# E-bookReader.net
KiCad netlist of a schematic drawn in EAGLE
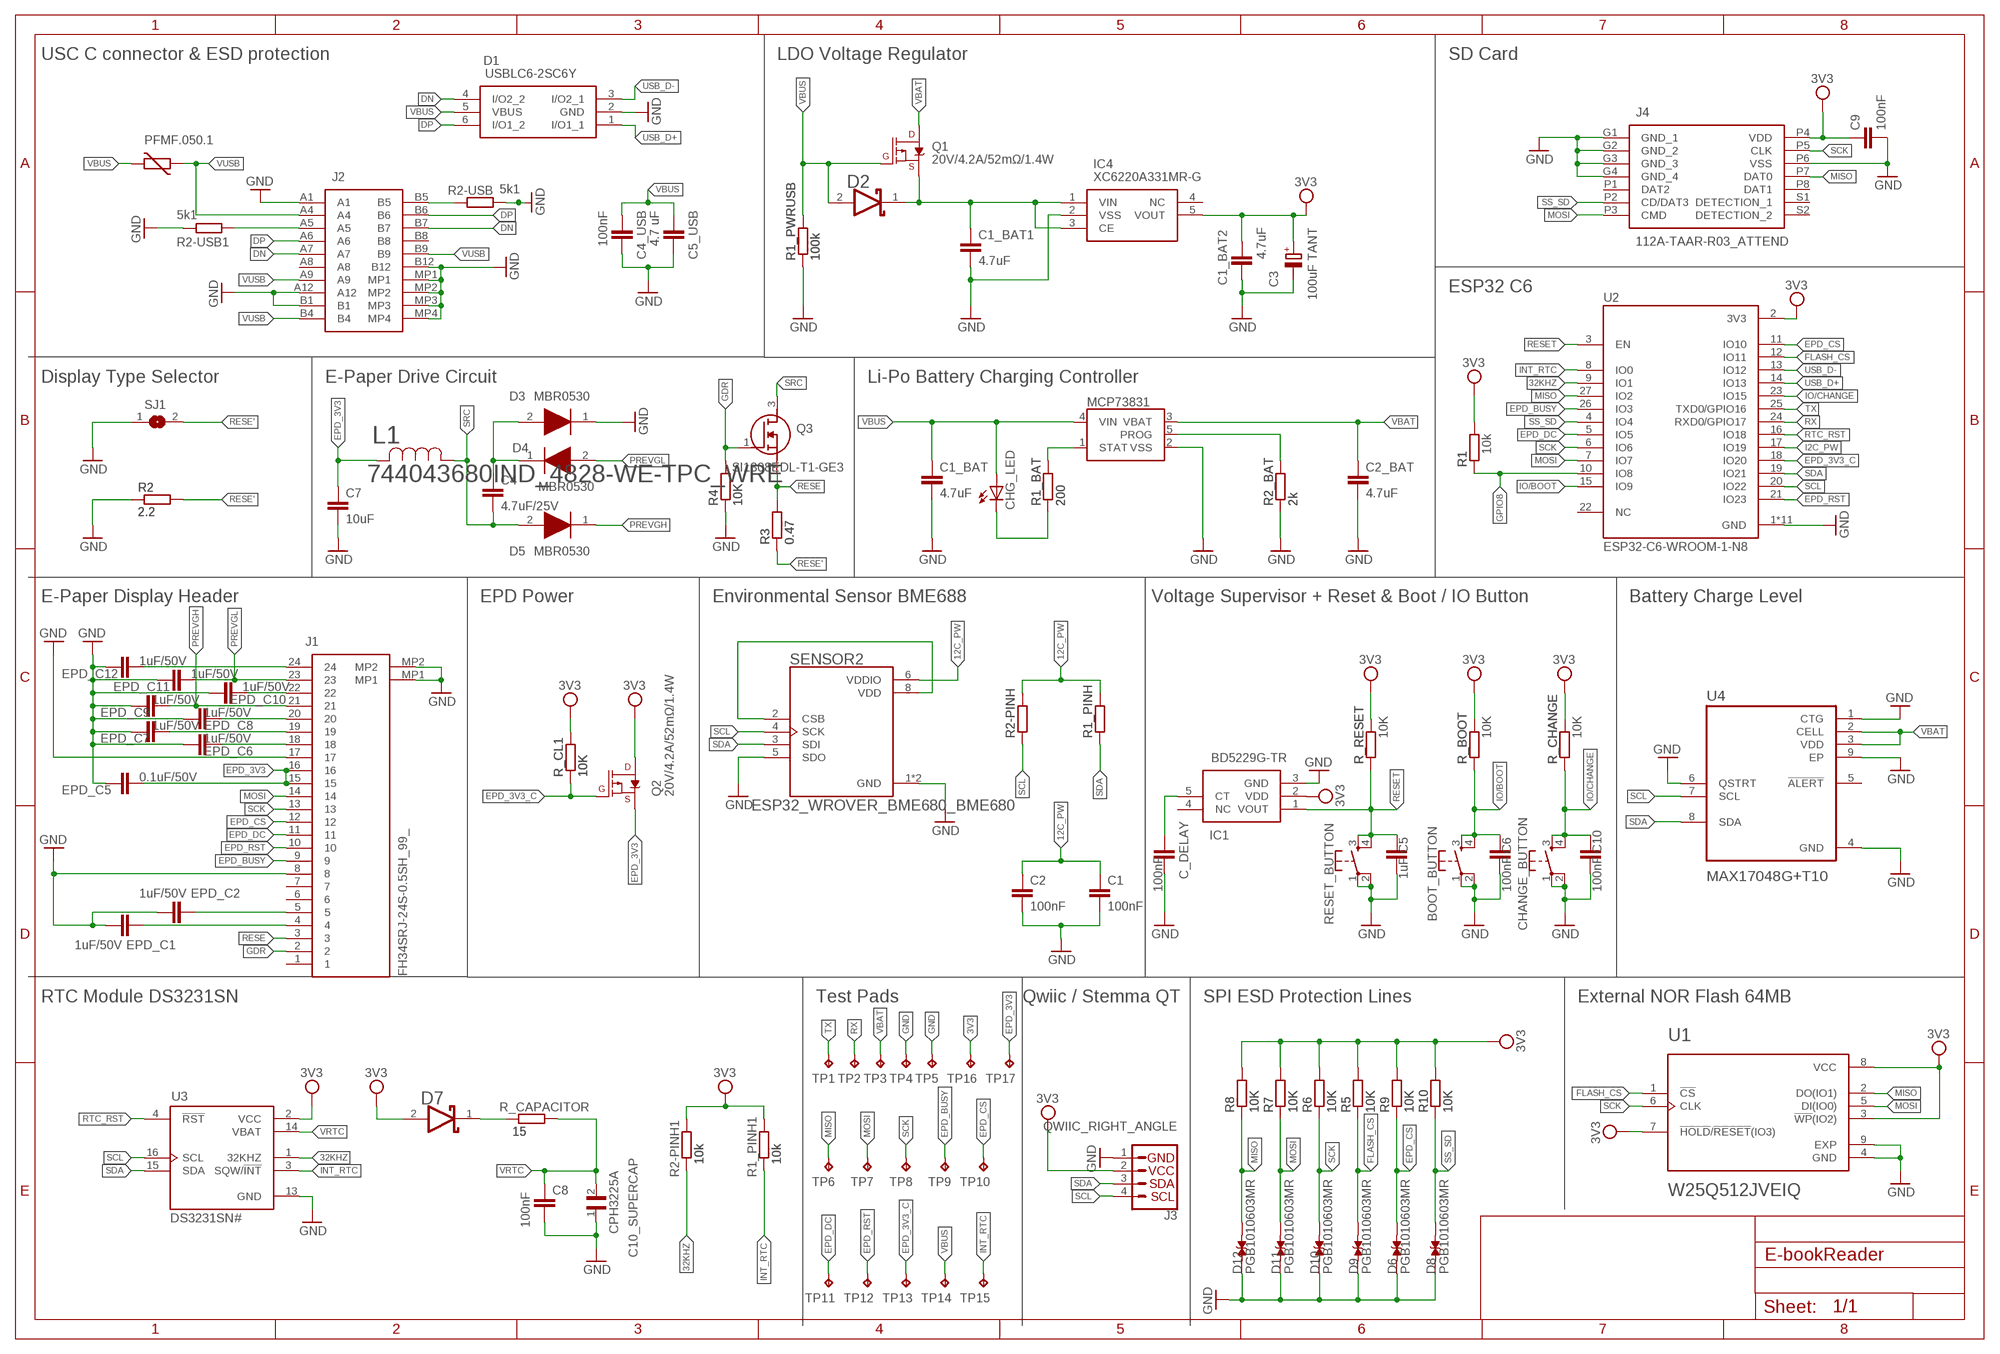
[diagram p0: schematic, sheet 1]

(export (version "E")
  (design (tool "Eeschema 10.0.6"))
  (components
    (comp (ref "BOOT_BUTTON")
      (value "BUTTON_CUSYOMV1")
      (footprint "eagle-import:MYBUTTON")
      (libsource (lib "eagle-import") (part "BUTTON_CUSYOMV1"))
    )
    (comp (ref "C1")
      (value "100nF")
      (footprint "eagle-import:EAGLE-LTSPICE_C0402")
      (libsource (lib "eagle-import") (part "EAGLE-LTSPICE_CC0402"))
    )
    (comp (ref "C1_BAT")
      (value "4.7uF")
      (footprint "eagle-import:EAGLE-LTSPICE_C0402")
      (libsource (lib "eagle-import") (part "EAGLE-LTSPICE_CC0402"))
    )
    (comp (ref "C1_BAT1")
      (value "4.7uF")
      (footprint "eagle-import:EAGLE-LTSPICE_C0402")
      (libsource (lib "eagle-import") (part "EAGLE-LTSPICE_CC0402"))
    )
    (comp (ref "C1_BAT2")
      (value "4.7uF")
      (footprint "eagle-import:EAGLE-LTSPICE_C0402")
      (libsource (lib "eagle-import") (part "EAGLE-LTSPICE_CC0402"))
    )
    (comp (ref "C2")
      (value "100nF")
      (footprint "eagle-import:EAGLE-LTSPICE_C0402")
      (libsource (lib "eagle-import") (part "EAGLE-LTSPICE_CC0402"))
    )
    (comp (ref "C2_BAT")
      (value "4.7uF")
      (footprint "eagle-import:EAGLE-LTSPICE_C0402")
      (libsource (lib "eagle-import") (part "EAGLE-LTSPICE_CC0402"))
    )
    (comp (ref "C3")
      (value "100uF TANT")
      (footprint "eagle-import:RCL_CT3528")
      (libsource (lib "eagle-import") (part "RCL_CPOL-EUCT3528"))
    )
    (comp (ref "C4")
      (value "4.7uF/25V")
      (footprint "eagle-import:EAGLE-LTSPICE_C0402")
      (libsource (lib "eagle-import") (part "EAGLE-LTSPICE_CC0402"))
    )
    (comp (ref "C4_USB")
      (value "100nF")
      (footprint "eagle-import:EAGLE-LTSPICE_C0402")
      (libsource (lib "eagle-import") (part "EAGLE-LTSPICE_CC0402"))
    )
    (comp (ref "C5")
      (value "1uF")
      (footprint "eagle-import:EAGLE-LTSPICE_C0402")
      (libsource (lib "eagle-import") (part "EAGLE-LTSPICE_CC0402"))
    )
    (comp (ref "C5_USB")
      (value "4.7 uF")
      (footprint "eagle-import:EAGLE-LTSPICE_C0402")
      (libsource (lib "eagle-import") (part "EAGLE-LTSPICE_CC0402"))
    )
    (comp (ref "C6")
      (value "100nF")
      (footprint "eagle-import:EAGLE-LTSPICE_C0402")
      (libsource (lib "eagle-import") (part "EAGLE-LTSPICE_CC0402"))
    )
    (comp (ref "C7")
      (value "10uF")
      (footprint "eagle-import:EAGLE-LTSPICE_C0402")
      (libsource (lib "eagle-import") (part "EAGLE-LTSPICE_CC0402"))
    )
    (comp (ref "C8")
      (value "100nF")
      (footprint "eagle-import:EAGLE-LTSPICE_C0402")
      (libsource (lib "eagle-import") (part "EAGLE-LTSPICE_CC0402"))
    )
    (comp (ref "C9")
      (value "100nF")
      (footprint "eagle-import:EAGLE-LTSPICE_C0402")
      (libsource (lib "eagle-import") (part "EAGLE-LTSPICE_CC0402"))
    )
    (comp (ref "C10")
      (value "100nF")
      (footprint "eagle-import:EAGLE-LTSPICE_C0402")
      (libsource (lib "eagle-import") (part "EAGLE-LTSPICE_CC0402"))
    )
    (comp (ref "C10_SUPERCAP")
      (value "CPH3225A")
      (footprint "eagle-import:CAPCP3225X100N")
      (fields (field (name "MF") "Seiko Instruments"))
      (libsource (lib "eagle-import") (part "CPH3225A"))
    )
    (comp (ref "CHANGE_BUTTON")
      (value "BUTTON_CUSYOMV1")
      (footprint "eagle-import:MYBUTTON")
      (libsource (lib "eagle-import") (part "BUTTON_CUSYOMV1"))
    )
    (comp (ref "CHG_LED")
      (value "ADAFRUIT_LEDCHIP-LED0603")
      (footprint "eagle-import:ADAFRUIT_CHIP-LED0603")
      (libsource (lib "eagle-import") (part "ADAFRUIT_LEDCHIP-LED0603"))
    )
    (comp (ref "C_DELAY")
      (value "100nF")
      (footprint "eagle-import:EAGLE-LTSPICE_C0402")
      (libsource (lib "eagle-import") (part "EAGLE-LTSPICE_CC0402"))
    )
    (comp (ref "D1")
      (value "USBLC6-2SC6Y")
      (footprint "eagle-import:SOT95P280X145-6N")
      (fields (field (name "MF") "STMicroelectronics"))
      (libsource (lib "eagle-import") (part "USBLC6-2SC6Y"))
    )
    (comp (ref "D2")
      (value "ESP32_WROVER_AVX---SD0805S020S1R0_AVX_SD0805S020S1R0_0_0AVX_SD0805S020S1R0_0_0")
      (footprint "eagle-import:ESP32_WROVER_AVX---SD0805S020S1R0_AVX_SD0805S020S1R0_0")
      (fields
        (field (name "DIGIKEY_PART_NUMBER") "478-7800-1-ND")
        (field (name "MF") "AVX")
        (field (name "MOUSER_PART_NUMBER") "581-SD0805S020S1R0")
      )
      (libsource (lib "eagle-import") (part "ESP32_WROVER_AVX---SD0805S020S1R0_AVX_SD0805S020S1R0_0_0AVX_SD0805S020S1R0_0_0"))
    )
    (comp (ref "D3")
      (value "MBR0530")
      (footprint "eagle-import:SOD3716X135N")
      (fields (field (name "MF") "ON Semiconductor"))
      (libsource (lib "eagle-import") (part "MBR0530"))
    )
    (comp (ref "D4")
      (value "MBR0530")
      (footprint "eagle-import:SOD3716X135N")
      (fields (field (name "MF") "ON Semiconductor"))
      (libsource (lib "eagle-import") (part "MBR0530"))
    )
    (comp (ref "D5")
      (value "MBR0530")
      (footprint "eagle-import:SOD3716X135N")
      (fields (field (name "MF") "ON Semiconductor"))
      (libsource (lib "eagle-import") (part "MBR0530"))
    )
    (comp (ref "D6")
      (value "PGB1010603MR")
      (footprint "eagle-import:DIOC1608X36N")
      (fields (field (name "MF") "Littelfuse Inc."))
      (libsource (lib "eagle-import") (part "PGB1010603MR"))
    )
    (comp (ref "D7")
      (value "ESP32_WROVER_AVX---SD0805S020S1R0_AVX_SD0805S020S1R0_0_0AVX_SD0805S020S1R0_0_0")
      (footprint "eagle-import:ESP32_WROVER_AVX---SD0805S020S1R0_AVX_SD0805S020S1R0_0")
      (fields
        (field (name "DIGIKEY_PART_NUMBER") "478-7800-1-ND")
        (field (name "MF") "AVX")
        (field (name "MOUSER_PART_NUMBER") "581-SD0805S020S1R0")
      )
      (libsource (lib "eagle-import") (part "ESP32_WROVER_AVX---SD0805S020S1R0_AVX_SD0805S020S1R0_0_0AVX_SD0805S020S1R0_0_0"))
    )
    (comp (ref "D8")
      (value "PGB1010603MR")
      (footprint "eagle-import:DIOC1608X36N")
      (fields (field (name "MF") "Littelfuse Inc."))
      (libsource (lib "eagle-import") (part "PGB1010603MR"))
    )
    (comp (ref "D9")
      (value "PGB1010603MR")
      (footprint "eagle-import:DIOC1608X36N")
      (fields (field (name "MF") "Littelfuse Inc."))
      (libsource (lib "eagle-import") (part "PGB1010603MR"))
    )
    (comp (ref "D10")
      (value "PGB1010603MR")
      (footprint "eagle-import:DIOC1608X36N")
      (fields (field (name "MF") "Littelfuse Inc."))
      (libsource (lib "eagle-import") (part "PGB1010603MR"))
    )
    (comp (ref "D11")
      (value "PGB1010603MR")
      (footprint "eagle-import:DIOC1608X36N")
      (fields (field (name "MF") "Littelfuse Inc."))
      (libsource (lib "eagle-import") (part "PGB1010603MR"))
    )
    (comp (ref "D12")
      (value "PGB1010603MR")
      (footprint "eagle-import:DIOC1608X36N")
      (fields (field (name "MF") "Littelfuse Inc."))
      (libsource (lib "eagle-import") (part "PGB1010603MR"))
    )
    (comp (ref "EPD_C1")
      (value "1uF/50V")
      (footprint "eagle-import:EAGLE-LTSPICE_C0402")
      (libsource (lib "eagle-import") (part "EAGLE-LTSPICE_CC0402"))
    )
    (comp (ref "EPD_C2")
      (value "1uF/50V")
      (footprint "eagle-import:EAGLE-LTSPICE_C0402")
      (libsource (lib "eagle-import") (part "EAGLE-LTSPICE_CC0402"))
    )
    (comp (ref "EPD_C5")
      (value "0.1uF/50V")
      (footprint "eagle-import:EAGLE-LTSPICE_C0402")
      (libsource (lib "eagle-import") (part "EAGLE-LTSPICE_CC0402"))
    )
    (comp (ref "EPD_C6")
      (value "1uF/50V")
      (footprint "eagle-import:EAGLE-LTSPICE_C0402")
      (libsource (lib "eagle-import") (part "EAGLE-LTSPICE_CC0402"))
    )
    (comp (ref "EPD_C7")
      (value "1uF/50V")
      (footprint "eagle-import:EAGLE-LTSPICE_C0402")
      (libsource (lib "eagle-import") (part "EAGLE-LTSPICE_CC0402"))
    )
    (comp (ref "EPD_C8")
      (value "1uF/50V")
      (footprint "eagle-import:EAGLE-LTSPICE_C0402")
      (libsource (lib "eagle-import") (part "EAGLE-LTSPICE_CC0402"))
    )
    (comp (ref "EPD_C9")
      (value "1uF/50V")
      (footprint "eagle-import:EAGLE-LTSPICE_C0402")
      (libsource (lib "eagle-import") (part "EAGLE-LTSPICE_CC0402"))
    )
    (comp (ref "EPD_C10")
      (value "1uF/50V")
      (footprint "eagle-import:EAGLE-LTSPICE_C0402")
      (libsource (lib "eagle-import") (part "EAGLE-LTSPICE_CC0402"))
    )
    (comp (ref "EPD_C11")
      (value "1uF/50V")
      (footprint "eagle-import:EAGLE-LTSPICE_C0402")
      (libsource (lib "eagle-import") (part "EAGLE-LTSPICE_CC0402"))
    )
    (comp (ref "EPD_C12")
      (value "1uF/50V")
      (footprint "eagle-import:EAGLE-LTSPICE_C0402")
      (libsource (lib "eagle-import") (part "EAGLE-LTSPICE_CC0402"))
    )
    (comp (ref "IC1")
      (value "BD5229G-TR")
      (footprint "eagle-import:SOT95P280X125-5N")
      (fields (field (name "MOUSER_PART_NUMBER") "755-BD5229G-TR"))
      (libsource (lib "eagle-import") (part "BD5229G-TR"))
    )
    (comp (ref "IC4")
      (value "XC6220A331MR-G")
      (footprint "eagle-import:SOT95P280X120-5N")
      (fields (field (name "MOUSER_PART_NUMBER") "865-XC6220A331MR-G"))
      (libsource (lib "eagle-import") (part "XC6220A331MR-G"))
    )
    (comp (ref "J1")
      (value "FH34SRJ-24S-0.5SH_99_")
      (footprint "eagle-import:FH34SRJ24S05SH99")
      (fields
        (field (name "MANUFACTURER_PART_NUMBER") "FH34SRJ-24S-0.5SH(99)")
        (field (name "MOUSER_PART_NUMBER") "798-FH34SRJ24S05SH99")
      )
      (libsource (lib "eagle-import") (part "FH34SRJ-24S-0.5SH_99_"))
    )
    (comp (ref "J2")
      (value "SAMACSYS_PARTS_USB4110-GF-A")
      (footprint "eagle-import:SAMACSYS_PARTS_USB4110GFA")
      (fields
        (field (name "MANUFACTURER_PART_NUMBER") "USB4110-GF-A")
        (field (name "MOUSER_PART_NUMBER") "640-USB4110-GF-A")
      )
      (libsource (lib "eagle-import") (part "SAMACSYS_PARTS_USB4110-GF-A"))
    )
    (comp (ref "J3")
      (value "QWIIC_RIGHT_ANGLE")
      (footprint "eagle-import:JST04_1MM_RA")
      (libsource (lib "eagle-import") (part "QWIIC_CONNECTORJS-1MM"))
    )
    (comp (ref "J4")
      (value "112A-TAAR-R03_ATTEND")
      (footprint "eagle-import:112ATAARR03ATTEND")
      (fields (field (name "MANUFACTURER_PART_NUMBER") "112A-TAAR-R03 ATTEND"))
      (libsource (lib "eagle-import") (part "112A-TAAR-R03_ATTEND"))
    )
    (comp (ref "L1")
      (value "744043680IND_4828-WE-TPC_WRE")
      (footprint "eagle-import:IND_4828-WE-TPC_WRE")
      (fields
        (field (name "MANUFACTURER_PART_NUMBER") "744043680")
        (field (name "COPYRIGHT") "Copyright (C) 2024 Ultra Librarian. All rights reserved.")
      )
      (libsource (lib "eagle-import") (part "744043680IND_4828-WE-TPC_WRE"))
    )
    (comp (ref "MCP73831")
      (value "ESP32_WROVER_SPARKFUN-IC-POWER_MCP73831")
      (footprint "eagle-import:ESP32_WROVER_SPARKFUN-IC-POWER_SOT23-5")
      (libsource (lib "eagle-import") (part "ESP32_WROVER_SPARKFUN-IC-POWER_MCP73831"))
    )
    (comp (ref "PFMF.050.1")
      (value "ESP32C6_VARISTORCN1812")
      (footprint "eagle-import:ESP32C6_VARISTOR_CT_CN1812")
      (libsource (lib "eagle-import") (part "ESP32C6_VARISTORCN1812"))
    )
    (comp (ref "Q1")
      (value "20V/4.2A/52mΩ/1.4W")
      (footprint "eagle-import:ESP32_WROVER_SPARKFUN-DISCRETESEMI_SOT23-3")
      (libsource (lib "eagle-import") (part "ESP32_WROVER_SPARKFUN-DISCRETESEMI_MOSFET_PCH-DMG2305UX-7"))
    )
    (comp (ref "Q2")
      (value "20V/4.2A/52mΩ/1.4W")
      (footprint "eagle-import:ESP32_WROVER_SPARKFUN-DISCRETESEMI_SOT23-3")
      (libsource (lib "eagle-import") (part "ESP32_WROVER_SPARKFUN-DISCRETESEMI_MOSFET_PCH-DMG2305UX-7"))
    )
    (comp (ref "Q3")
      (value "SI1308EDL-T1-GE3")
      (footprint "eagle-import:SOT65P210X110-3N")
      (fields (field (name "MF") "Vishay Siliconix"))
      (libsource (lib "eagle-import") (part "SI1308EDL-T1-GE3"))
    )
    (comp (ref "R1")
      (value "10k")
      (footprint "eagle-import:ESP32_WROVER_EAGLE-LTSPICE_R0402")
      (libsource (lib "eagle-import") (part "ESP32_WROVER_EAGLE-LTSPICE_RR0402"))
    )
    (comp (ref "R1_BAT")
      (value "200")
      (footprint "eagle-import:ESP32_WROVER_EAGLE-LTSPICE_R0402")
      (libsource (lib "eagle-import") (part "ESP32_WROVER_EAGLE-LTSPICE_RR0402"))
    )
    (comp (ref "R1_PINH")
      (value "ESP32_WROVER_EAGLE-LTSPICE_RR0402")
      (footprint "eagle-import:ESP32_WROVER_EAGLE-LTSPICE_R0402")
      (libsource (lib "eagle-import") (part "ESP32_WROVER_EAGLE-LTSPICE_RR0402"))
    )
    (comp (ref "R1_PINH1")
      (value "10k")
      (footprint "eagle-import:ESP32_WROVER_EAGLE-LTSPICE_R0402")
      (libsource (lib "eagle-import") (part "ESP32_WROVER_EAGLE-LTSPICE_RR0402"))
    )
    (comp (ref "R1_PWRUSB")
      (value "100k")
      (footprint "eagle-import:ESP32_WROVER_EAGLE-LTSPICE_R0402")
      (libsource (lib "eagle-import") (part "ESP32_WROVER_EAGLE-LTSPICE_RR0402"))
    )
    (comp (ref "R2")
      (value "2.2")
      (footprint "eagle-import:ESP32_WROVER_EAGLE-LTSPICE_R0402")
      (libsource (lib "eagle-import") (part "ESP32_WROVER_EAGLE-LTSPICE_RR0402"))
    )
    (comp (ref "R2-PINH")
      (value "ESP32_WROVER_EAGLE-LTSPICE_RR0402")
      (footprint "eagle-import:ESP32_WROVER_EAGLE-LTSPICE_R0402")
      (libsource (lib "eagle-import") (part "ESP32_WROVER_EAGLE-LTSPICE_RR0402"))
    )
    (comp (ref "R2-PINH1")
      (value "10k")
      (footprint "eagle-import:ESP32_WROVER_EAGLE-LTSPICE_R0402")
      (libsource (lib "eagle-import") (part "ESP32_WROVER_EAGLE-LTSPICE_RR0402"))
    )
    (comp (ref "R2-USB")
      (value "5k1")
      (footprint "eagle-import:ESP32_WROVER_EAGLE-LTSPICE_R0402")
      (libsource (lib "eagle-import") (part "ESP32_WROVER_EAGLE-LTSPICE_RR0402"))
    )
    (comp (ref "R2-USB1")
      (value "5k1")
      (footprint "eagle-import:ESP32_WROVER_EAGLE-LTSPICE_R0402")
      (libsource (lib "eagle-import") (part "ESP32_WROVER_EAGLE-LTSPICE_RR0402"))
    )
    (comp (ref "R2_BAT")
      (value "2k")
      (footprint "eagle-import:ESP32_WROVER_EAGLE-LTSPICE_R0402")
      (libsource (lib "eagle-import") (part "ESP32_WROVER_EAGLE-LTSPICE_RR0402"))
    )
    (comp (ref "R3")
      (value "0.47")
      (footprint "eagle-import:ESP32_WROVER_EAGLE-LTSPICE_R0402")
      (libsource (lib "eagle-import") (part "ESP32_WROVER_EAGLE-LTSPICE_RR0402"))
    )
    (comp (ref "R4")
      (value "10K")
      (footprint "eagle-import:ESP32_WROVER_EAGLE-LTSPICE_R0402")
      (libsource (lib "eagle-import") (part "ESP32_WROVER_EAGLE-LTSPICE_RR0402"))
    )
    (comp (ref "R5")
      (value "10K")
      (footprint "eagle-import:ESP32_WROVER_EAGLE-LTSPICE_R0402")
      (libsource (lib "eagle-import") (part "ESP32_WROVER_EAGLE-LTSPICE_RR0402"))
    )
    (comp (ref "R6")
      (value "10K")
      (footprint "eagle-import:ESP32_WROVER_EAGLE-LTSPICE_R0402")
      (libsource (lib "eagle-import") (part "ESP32_WROVER_EAGLE-LTSPICE_RR0402"))
    )
    (comp (ref "R7")
      (value "10K")
      (footprint "eagle-import:ESP32_WROVER_EAGLE-LTSPICE_R0402")
      (libsource (lib "eagle-import") (part "ESP32_WROVER_EAGLE-LTSPICE_RR0402"))
    )
    (comp (ref "R8")
      (value "10K")
      (footprint "eagle-import:ESP32_WROVER_EAGLE-LTSPICE_R0402")
      (libsource (lib "eagle-import") (part "ESP32_WROVER_EAGLE-LTSPICE_RR0402"))
    )
    (comp (ref "R9")
      (value "10K")
      (footprint "eagle-import:ESP32_WROVER_EAGLE-LTSPICE_R0402")
      (libsource (lib "eagle-import") (part "ESP32_WROVER_EAGLE-LTSPICE_RR0402"))
    )
    (comp (ref "R10")
      (value "10K")
      (footprint "eagle-import:ESP32_WROVER_EAGLE-LTSPICE_R0402")
      (libsource (lib "eagle-import") (part "ESP32_WROVER_EAGLE-LTSPICE_RR0402"))
    )
    (comp (ref "RESET_BUTTON")
      (value "BUTTON_CUSYOMV1")
      (footprint "eagle-import:MYBUTTON")
      (libsource (lib "eagle-import") (part "BUTTON_CUSYOMV1"))
    )
    (comp (ref "R_BOOT")
      (value "10K")
      (footprint "eagle-import:ESP32_WROVER_EAGLE-LTSPICE_R0402")
      (libsource (lib "eagle-import") (part "ESP32_WROVER_EAGLE-LTSPICE_RR0402"))
    )
    (comp (ref "R_CAPACITOR")
      (value "15")
      (footprint "eagle-import:ESP32_WROVER_EAGLE-LTSPICE_R0402")
      (libsource (lib "eagle-import") (part "ESP32_WROVER_EAGLE-LTSPICE_RR0402"))
    )
    (comp (ref "R_CHANGE")
      (value "10K")
      (footprint "eagle-import:ESP32_WROVER_EAGLE-LTSPICE_R0402")
      (libsource (lib "eagle-import") (part "ESP32_WROVER_EAGLE-LTSPICE_RR0402"))
    )
    (comp (ref "R_CL1")
      (value "10K")
      (footprint "eagle-import:ESP32_WROVER_EAGLE-LTSPICE_R0402")
      (libsource (lib "eagle-import") (part "ESP32_WROVER_EAGLE-LTSPICE_RR0402"))
    )
    (comp (ref "R_RESET")
      (value "10K")
      (footprint "eagle-import:ESP32_WROVER_EAGLE-LTSPICE_R0402")
      (libsource (lib "eagle-import") (part "ESP32_WROVER_EAGLE-LTSPICE_RR0402"))
    )
    (comp (ref "SENSOR2")
      (value "ESP32_WROVER_BME680_BME680")
      (footprint "eagle-import:ESP32_WROVER_BME680_PSON80P300X300X100-8N")
      (fields (field (name "MF") "Bosch Sensortec") (field (name "MP") "BME680"))
      (libsource (lib "eagle-import") (part "ESP32_WROVER_BME680_BME680"))
    )
    (comp (ref "SJ1") (value "SJ") (footprint "eagle-import:SJ") (libsource (lib "eagle-import") (part "SJ")))
    (comp (ref "TP1")
      (value "TPTP20R")
      (footprint "eagle-import:TP20R")
      (libsource (lib "eagle-import") (part "TPTP20R"))
    )
    (comp (ref "TP2")
      (value "TPTP20R")
      (footprint "eagle-import:TP20R")
      (libsource (lib "eagle-import") (part "TPTP20R"))
    )
    (comp (ref "TP3")
      (value "TPTP20R")
      (footprint "eagle-import:TP20R")
      (libsource (lib "eagle-import") (part "TPTP20R"))
    )
    (comp (ref "TP4")
      (value "TPTP20R")
      (footprint "eagle-import:TP20R")
      (libsource (lib "eagle-import") (part "TPTP20R"))
    )
    (comp (ref "TP5")
      (value "TPTP20R")
      (footprint "eagle-import:TP20R")
      (libsource (lib "eagle-import") (part "TPTP20R"))
    )
    (comp (ref "TP6")
      (value "TPTP20R")
      (footprint "eagle-import:TP20R")
      (libsource (lib "eagle-import") (part "TPTP20R"))
    )
    (comp (ref "TP7")
      (value "TPTP20R")
      (footprint "eagle-import:TP20R")
      (libsource (lib "eagle-import") (part "TPTP20R"))
    )
    (comp (ref "TP8")
      (value "TPTP20R")
      (footprint "eagle-import:TP20R")
      (libsource (lib "eagle-import") (part "TPTP20R"))
    )
    (comp (ref "TP9")
      (value "TPTP20R")
      (footprint "eagle-import:TP20R")
      (libsource (lib "eagle-import") (part "TPTP20R"))
    )
    (comp (ref "TP10")
      (value "TPTP20R")
      (footprint "eagle-import:TP20R")
      (libsource (lib "eagle-import") (part "TPTP20R"))
    )
    (comp (ref "TP11")
      (value "TPTP20R")
      (footprint "eagle-import:TP20R")
      (libsource (lib "eagle-import") (part "TPTP20R"))
    )
    (comp (ref "TP12")
      (value "TPTP20R")
      (footprint "eagle-import:TP20R")
      (libsource (lib "eagle-import") (part "TPTP20R"))
    )
    (comp (ref "TP13")
      (value "TPTP20R")
      (footprint "eagle-import:TP20R")
      (libsource (lib "eagle-import") (part "TPTP20R"))
    )
    (comp (ref "TP14")
      (value "TPTP20R")
      (footprint "eagle-import:TP20R")
      (libsource (lib "eagle-import") (part "TPTP20R"))
    )
    (comp (ref "TP15")
      (value "TPTP20R")
      (footprint "eagle-import:TP20R")
      (libsource (lib "eagle-import") (part "TPTP20R"))
    )
    (comp (ref "TP16")
      (value "TPTP20R")
      (footprint "eagle-import:TP20R")
      (libsource (lib "eagle-import") (part "TPTP20R"))
    )
    (comp (ref "TP17")
      (value "TPTP20R")
      (footprint "eagle-import:TP20R")
      (libsource (lib "eagle-import") (part "TPTP20R"))
    )
    (comp (ref "U1")
      (value "W25Q512JVEIQ")
      (footprint "eagle-import:SON127P600X800X80-9N")
      (fields (field (name "MF") "Winbond Electronics"))
      (libsource (lib "eagle-import") (part "W25Q512JVEIQ"))
    )
    (comp (ref "U2")
      (value "ESP32-C6-WROOM-1-N8")
      (footprint "eagle-import:XCVR_ESP32-C6-WROOM-1-N8")
      (fields (field (name "MF") "Espressif Systems"))
      (libsource (lib "eagle-import") (part "ESP32-C6-WROOM-1-N8"))
    )
    (comp (ref "U3")
      (value "DS3231SN#")
      (footprint "eagle-import:SOIC127P1032X265-16N")
      (fields (field (name "MF") "Analog Devices"))
      (libsource (lib "eagle-import") (part "DS3231SN#"))
    )
    (comp (ref "U4")
      (value "MAX17048G+T10")
      (footprint "eagle-import:SON50P200X200X80-9N")
      (fields (field (name "MF") "Analog Devices"))
      (libsource (lib "eagle-import") (part "MAX17048G+T10"))
    )
  )
  (nets
    (net (code "1") (name "3V3") (class "Default")
      (node (ref "C1_BAT2") (pin "1") (pinfunction "1_1") (pintype "passive"))
      (node (ref "C3") (pin "+") (pinfunction "+_+") (pintype "passive"))
      (node (ref "C9") (pin "1") (pinfunction "1_1") (pintype "passive"))
      (node (ref "D7") (pin "2") (pinfunction "ANODE_2") (pintype "bidirectional"))
      (node (ref "IC1") (pin "2") (pinfunction "VDD_2") (pintype "bidirectional"))
      (node (ref "IC4") (pin "5") (pinfunction "VOUT_5") (pintype "bidirectional"))
      (node (ref "J3") (pin "2") (pinfunction "2_2") (pintype "power_in"))
      (node (ref "J4") (pin "P4") (pinfunction "VDD_P4") (pintype "bidirectional"))
      (node (ref "Q2") (pin "3") (pinfunction "D_3") (pintype "bidirectional"))
      (node (ref "R1") (pin "2") (pinfunction "2_2") (pintype "passive"))
      (node (ref "R10") (pin "2") (pinfunction "2_2") (pintype "passive"))
      (node (ref "R1_PINH1") (pin "2") (pinfunction "2_2") (pintype "passive"))
      (node (ref "R2-PINH1") (pin "2") (pinfunction "2_2") (pintype "passive"))
      (node (ref "R5") (pin "2") (pinfunction "2_2") (pintype "passive"))
      (node (ref "R6") (pin "2") (pinfunction "2_2") (pintype "passive"))
      (node (ref "R7") (pin "2") (pinfunction "2_2") (pintype "passive"))
      (node (ref "R8") (pin "2") (pinfunction "2_2") (pintype "passive"))
      (node (ref "R9") (pin "2") (pinfunction "2_2") (pintype "passive"))
      (node (ref "R_BOOT") (pin "2") (pinfunction "2_2") (pintype "passive"))
      (node (ref "R_CHANGE") (pin "2") (pinfunction "2_2") (pintype "passive"))
      (node (ref "R_CL1") (pin "2") (pinfunction "2_2") (pintype "passive"))
      (node (ref "R_RESET") (pin "2") (pinfunction "2_2") (pintype "passive"))
      (node (ref "TP16") (pin "TP") (pinfunction "TP_TP") (pintype "input"))
      (node (ref "U1") (pin "3") (pinfunction "~{WP}(IO2)_3") (pintype "bidirectional"))
      (node (ref "U1") (pin "7") (pinfunction "~{HOLD}/~{RESET}(IO3)_7") (pintype "bidirectional"))
      (node (ref "U1") (pin "8") (pinfunction "VCC_8") (pintype "power_in"))
      (node (ref "U2") (pin "2") (pinfunction "3V3_2") (pintype "power_in"))
      (node (ref "U3") (pin "2") (pinfunction "VCC_2") (pintype "power_in"))
    )
    (net (code "2") (name "12C_PW") (class "Default")
      (node (ref "C1") (pin "1") (pinfunction "1_1") (pintype "passive"))
      (node (ref "C2") (pin "1") (pinfunction "1_1") (pintype "passive"))
      (node (ref "R1_PINH") (pin "2") (pinfunction "2_2") (pintype "passive"))
      (node (ref "R2-PINH") (pin "2") (pinfunction "2_2") (pintype "passive"))
      (node (ref "SENSOR2") (pin "6") (pinfunction "VDDIO_6") (pintype "power_in"))
    )
    (net (code "3") (name "32KHZ") (class "Default")
      (node (ref "R2-PINH1") (pin "1") (pinfunction "1_1") (pintype "passive"))
      (node (ref "U2") (pin "9") (pinfunction "IO1_9") (pintype "bidirectional"))
      (node (ref "U3") (pin "1") (pinfunction "32KHZ_1") (pintype "output"))
    )
    (net (code "4") (name "DN") (class "Default")
      (node (ref "D1") (pin "4") (pinfunction "I/O2_2_4") (pintype "bidirectional"))
      (node (ref "J2") (pin "A7") (pinfunction "A7_A7") (pintype "bidirectional"))
      (node (ref "J2") (pin "B7") (pinfunction "B7_B7") (pintype "bidirectional"))
    )
    (net (code "5") (name "DP") (class "Default")
      (node (ref "D1") (pin "6") (pinfunction "I/O1_2_6") (pintype "bidirectional"))
      (node (ref "J2") (pin "A6") (pinfunction "A6_A6") (pintype "bidirectional"))
      (node (ref "J2") (pin "B6") (pinfunction "B6_B6") (pintype "bidirectional"))
    )
    (net (code "6") (name "EPD_3V3") (class "Default")
      (node (ref "C7") (pin "1") (pinfunction "1_1") (pintype "passive"))
      (node (ref "EPD_C5") (pin "1") (pinfunction "1_1") (pintype "passive"))
      (node (ref "J1") (pin "15") (pinfunction "15_15") (pintype "bidirectional"))
      (node (ref "J1") (pin "16") (pinfunction "16_16") (pintype "bidirectional"))
      (node (ref "L1") (pin "2") (pinfunction "2_2") (pintype "passive"))
      (node (ref "Q2") (pin "2") (pinfunction "S_2") (pintype "bidirectional"))
      (node (ref "TP17") (pin "TP") (pinfunction "TP_TP") (pintype "input"))
    )
    (net (code "7") (name "EPD_3V3_C") (class "Default")
      (node (ref "Q2") (pin "1") (pinfunction "G_1") (pintype "bidirectional"))
      (node (ref "R_CL1") (pin "1") (pinfunction "1_1") (pintype "passive"))
      (node (ref "TP13") (pin "TP") (pinfunction "TP_TP") (pintype "input"))
      (node (ref "U2") (pin "18") (pinfunction "IO20_18") (pintype "bidirectional"))
    )
    (net (code "8") (name "EPD_BUSY") (class "Default")
      (node (ref "J1") (pin "9") (pinfunction "9_9") (pintype "bidirectional"))
      (node (ref "TP9") (pin "TP") (pinfunction "TP_TP") (pintype "input"))
      (node (ref "U2") (pin "26") (pinfunction "IO3_26") (pintype "bidirectional"))
    )
    (net (code "9") (name "EPD_CS") (class "Default")
      (node (ref "D6") (pin "2") (pinfunction "2_2") (pintype "passive"))
      (node (ref "J1") (pin "12") (pinfunction "12_12") (pintype "bidirectional"))
      (node (ref "R9") (pin "1") (pinfunction "1_1") (pintype "passive"))
      (node (ref "TP10") (pin "TP") (pinfunction "TP_TP") (pintype "input"))
      (node (ref "U2") (pin "11") (pinfunction "IO10_11") (pintype "bidirectional"))
    )
    (net (code "10") (name "EPD_DC") (class "Default")
      (node (ref "J1") (pin "11") (pinfunction "11_11") (pintype "bidirectional"))
      (node (ref "TP11") (pin "TP") (pinfunction "TP_TP") (pintype "input"))
      (node (ref "U2") (pin "5") (pinfunction "IO5_5") (pintype "bidirectional"))
    )
    (net (code "11") (name "EPD_RST") (class "Default")
      (node (ref "J1") (pin "10") (pinfunction "10_10") (pintype "bidirectional"))
      (node (ref "TP12") (pin "TP") (pinfunction "TP_TP") (pintype "input"))
      (node (ref "U2") (pin "21") (pinfunction "IO23_21") (pintype "bidirectional"))
    )
    (net (code "12") (name "FLASH_CS") (class "Default")
      (node (ref "D9") (pin "2") (pinfunction "2_2") (pintype "passive"))
      (node (ref "R5") (pin "1") (pinfunction "1_1") (pintype "passive"))
      (node (ref "U1") (pin "1") (pinfunction "~{CS}_1") (pintype "input"))
      (node (ref "U2") (pin "12") (pinfunction "IO11_12") (pintype "bidirectional"))
    )
    (net (code "13") (name "GDR") (class "Default")
      (node (ref "J1") (pin "2") (pinfunction "2_2") (pintype "bidirectional"))
      (node (ref "Q3") (pin "1") (pinfunction "G_1") (pintype "bidirectional"))
      (node (ref "R4") (pin "2") (pinfunction "2_2") (pintype "passive"))
    )
    (net (code "14") (name "GND") (class "Default")
      (node (ref "BOOT_BUTTON") (pin "1") (pinfunction "1_1") (pintype "passive"))
      (node (ref "BOOT_BUTTON") (pin "2") (pinfunction "2_2") (pintype "passive"))
      (node (ref "C1") (pin "2") (pinfunction "2_2") (pintype "passive"))
      (node (ref "C10") (pin "2") (pinfunction "2_2") (pintype "passive"))
      (node (ref "C10_SUPERCAP") (pin "1") (pinfunction "1_1") (pintype "passive"))
      (node (ref "C1_BAT") (pin "2") (pinfunction "2_2") (pintype "passive"))
      (node (ref "C1_BAT1") (pin "2") (pinfunction "2_2") (pintype "passive"))
      (node (ref "C1_BAT2") (pin "2") (pinfunction "2_2") (pintype "passive"))
      (node (ref "C2") (pin "2") (pinfunction "2_2") (pintype "passive"))
      (node (ref "C2_BAT") (pin "2") (pinfunction "2_2") (pintype "passive"))
      (node (ref "C3") (pin "-") (pinfunction "-_-") (pintype "passive"))
      (node (ref "C4_USB") (pin "2") (pinfunction "2_2") (pintype "passive"))
      (node (ref "C5") (pin "2") (pinfunction "2_2") (pintype "passive"))
      (node (ref "C5_USB") (pin "2") (pinfunction "2_2") (pintype "passive"))
      (node (ref "C6") (pin "2") (pinfunction "2_2") (pintype "passive"))
      (node (ref "C7") (pin "2") (pinfunction "2_2") (pintype "passive"))
      (node (ref "C8") (pin "2") (pinfunction "2_2") (pintype "passive"))
      (node (ref "C9") (pin "2") (pinfunction "2_2") (pintype "passive"))
      (node (ref "CHANGE_BUTTON") (pin "1") (pinfunction "1_1") (pintype "passive"))
      (node (ref "CHANGE_BUTTON") (pin "2") (pinfunction "2_2") (pintype "passive"))
      (node (ref "C_DELAY") (pin "2") (pinfunction "2_2") (pintype "passive"))
      (node (ref "D1") (pin "2") (pinfunction "GND_2") (pintype "bidirectional"))
      (node (ref "D10") (pin "1") (pinfunction "1_1") (pintype "passive"))
      (node (ref "D11") (pin "1") (pinfunction "1_1") (pintype "passive"))
      (node (ref "D12") (pin "1") (pinfunction "1_1") (pintype "passive"))
      (node (ref "D3") (pin "1") (pinfunction "K_1") (pintype "bidirectional"))
      (node (ref "D6") (pin "1") (pinfunction "1_1") (pintype "passive"))
      (node (ref "D8") (pin "1") (pinfunction "1_1") (pintype "passive"))
      (node (ref "D9") (pin "1") (pinfunction "1_1") (pintype "passive"))
      (node (ref "EPD_C1") (pin "2") (pinfunction "2_2") (pintype "passive"))
      (node (ref "EPD_C10") (pin "2") (pinfunction "2_2") (pintype "passive"))
      (node (ref "EPD_C11") (pin "2") (pinfunction "2_2") (pintype "passive"))
      (node (ref "EPD_C12") (pin "2") (pinfunction "2_2") (pintype "passive"))
      (node (ref "EPD_C2") (pin "2") (pinfunction "2_2") (pintype "passive"))
      (node (ref "EPD_C5") (pin "2") (pinfunction "2_2") (pintype "passive"))
      (node (ref "EPD_C6") (pin "2") (pinfunction "2_2") (pintype "passive"))
      (node (ref "EPD_C7") (pin "2") (pinfunction "2_2") (pintype "passive"))
      (node (ref "EPD_C8") (pin "2") (pinfunction "2_2") (pintype "passive"))
      (node (ref "EPD_C9") (pin "2") (pinfunction "2_2") (pintype "passive"))
      (node (ref "IC1") (pin "3") (pinfunction "GND_3") (pintype "bidirectional"))
      (node (ref "IC4") (pin "2") (pinfunction "VSS_2") (pintype "bidirectional"))
      (node (ref "J1") (pin "17") (pinfunction "17_17") (pintype "bidirectional"))
      (node (ref "J1") (pin "8") (pinfunction "8_8") (pintype "bidirectional"))
      (node (ref "J1") (pin "MP1") (pinfunction "MP1_MP1") (pintype "bidirectional"))
      (node (ref "J1") (pin "MP2") (pinfunction "MP2_MP2") (pintype "bidirectional"))
      (node (ref "J2") (pin "A1") (pinfunction "A1_A1") (pintype "bidirectional"))
      (node (ref "J2") (pin "A12") (pinfunction "A12_A12") (pintype "bidirectional"))
      (node (ref "J2") (pin "B1") (pinfunction "B1_B1") (pintype "bidirectional"))
      (node (ref "J2") (pin "B12") (pinfunction "B12_B12") (pintype "bidirectional"))
      (node (ref "J2") (pin "MP1") (pinfunction "MP1_MP1") (pintype "bidirectional"))
      (node (ref "J2") (pin "MP2") (pinfunction "MP2_MP2") (pintype "bidirectional"))
      (node (ref "J2") (pin "MP3") (pinfunction "MP3_MP3") (pintype "bidirectional"))
      (node (ref "J2") (pin "MP4") (pinfunction "MP4_MP4") (pintype "bidirectional"))
      (node (ref "J3") (pin "1") (pinfunction "1_1") (pintype "power_in"))
      (node (ref "J4") (pin "G1") (pinfunction "GND_1_G1") (pintype "bidirectional"))
      (node (ref "J4") (pin "G2") (pinfunction "GND_2_G2") (pintype "bidirectional"))
      (node (ref "J4") (pin "G3") (pinfunction "GND_3_G3") (pintype "bidirectional"))
      (node (ref "J4") (pin "G4") (pinfunction "GND_4_G4") (pintype "bidirectional"))
      (node (ref "J4") (pin "P6") (pinfunction "VSS_P6") (pintype "bidirectional"))
      (node (ref "MCP73831") (pin "2") (pinfunction "VSS_2") (pintype "power_in"))
      (node (ref "R1_PWRUSB") (pin "1") (pinfunction "1_1") (pintype "passive"))
      (node (ref "R2") (pin "1") (pinfunction "1_1") (pintype "passive"))
      (node (ref "R2-USB") (pin "2") (pinfunction "2_2") (pintype "passive"))
      (node (ref "R2-USB1") (pin "1") (pinfunction "1_1") (pintype "passive"))
      (node (ref "R2_BAT") (pin "1") (pinfunction "1_1") (pintype "passive"))
      (node (ref "R4") (pin "1") (pinfunction "1_1") (pintype "passive"))
      (node (ref "RESET_BUTTON") (pin "1") (pinfunction "1_1") (pintype "passive"))
      (node (ref "RESET_BUTTON") (pin "2") (pinfunction "2_2") (pintype "passive"))
      (node (ref "SENSOR2") (pin "1") (pinfunction "GND_1") (pintype "power_in"))
      (node (ref "SENSOR2") (pin "5") (pinfunction "SDO_5") (pintype "bidirectional"))
      (node (ref "SENSOR2") (pin "7") (pinfunction "GND_7") (pintype "power_in"))
      (node (ref "SJ1") (pin "1") (pinfunction "1_1") (pintype "passive"))
      (node (ref "TP4") (pin "TP") (pinfunction "TP_TP") (pintype "input"))
      (node (ref "TP5") (pin "TP") (pinfunction "TP_TP") (pintype "input"))
      (node (ref "U1") (pin "4") (pinfunction "GND_4") (pintype "power_in"))
      (node (ref "U1") (pin "9") (pinfunction "EXP_9") (pintype "passive"))
      (node (ref "U2") (pin "1") (pinfunction "GND_1") (pintype "power_in"))
      (node (ref "U2") (pin "28") (pinfunction "GND_28") (pintype "power_in"))
      (node (ref "U2") (pin "29_1") (pinfunction "GND_29_1") (pintype "power_in"))
      (node (ref "U2") (pin "29_2") (pinfunction "GND_29_2") (pintype "power_in"))
      (node (ref "U2") (pin "29_3") (pinfunction "GND_29_3") (pintype "power_in"))
      (node (ref "U2") (pin "29_4") (pinfunction "GND_29_4") (pintype "power_in"))
      (node (ref "U2") (pin "29_5") (pinfunction "GND_29_5") (pintype "power_in"))
      (node (ref "U2") (pin "29_6") (pinfunction "GND_29_6") (pintype "power_in"))
      (node (ref "U2") (pin "29_7") (pinfunction "GND_29_7") (pintype "power_in"))
      (node (ref "U2") (pin "29_8") (pinfunction "GND_29_8") (pintype "power_in"))
      (node (ref "U2") (pin "29_9") (pinfunction "GND_29_9") (pintype "power_in"))
      (node (ref "U3") (pin "13") (pinfunction "GND_13") (pintype "power_in"))
      (node (ref "U4") (pin "1") (pinfunction "CTG_1") (pintype "power_in"))
      (node (ref "U4") (pin "4") (pinfunction "GND_4") (pintype "power_in"))
      (node (ref "U4") (pin "6") (pinfunction "QSTRT_6") (pintype "input"))
      (node (ref "U4") (pin "9") (pinfunction "EP_9") (pintype "power_in"))
    )
    (net (code "15") (name "GPIO8") (class "Default")
      (node (ref "R1") (pin "1") (pinfunction "1_1") (pintype "passive"))
      (node (ref "U2") (pin "10") (pinfunction "IO8_10") (pintype "bidirectional"))
    )
    (net (code "16") (name "I2C_PW") (class "Default")
      (node (ref "U2") (pin "17") (pinfunction "IO19_17") (pintype "bidirectional"))
    )
    (net (code "17") (name "INT_RTC") (class "Default")
      (node (ref "R1_PINH1") (pin "1") (pinfunction "1_1") (pintype "passive"))
      (node (ref "TP15") (pin "TP") (pinfunction "TP_TP") (pintype "input"))
      (node (ref "U2") (pin "8") (pinfunction "IO0_8") (pintype "bidirectional"))
      (node (ref "U3") (pin "3") (pinfunction "SQW/~{INT}_3") (pintype "output"))
    )
    (net (code "18") (name "IO{slash}BOOT") (class "Default")
      (node (ref "BOOT_BUTTON") (pin "3") (pinfunction "3_3") (pintype "passive"))
      (node (ref "BOOT_BUTTON") (pin "4") (pinfunction "4_4") (pintype "passive"))
      (node (ref "C6") (pin "1") (pinfunction "1_1") (pintype "passive"))
      (node (ref "R_BOOT") (pin "1") (pinfunction "1_1") (pintype "passive"))
      (node (ref "U2") (pin "15") (pinfunction "IO9_15") (pintype "bidirectional"))
    )
    (net (code "19") (name "IO{slash}CHANGE") (class "Default")
      (node (ref "C10") (pin "1") (pinfunction "1_1") (pintype "passive"))
      (node (ref "CHANGE_BUTTON") (pin "3") (pinfunction "3_3") (pintype "passive"))
      (node (ref "CHANGE_BUTTON") (pin "4") (pinfunction "4_4") (pintype "passive"))
      (node (ref "R_CHANGE") (pin "1") (pinfunction "1_1") (pintype "passive"))
      (node (ref "U2") (pin "23") (pinfunction "IO15_23") (pintype "bidirectional"))
    )
    (net (code "20") (name "MISO") (class "Default")
      (node (ref "D12") (pin "2") (pinfunction "2_2") (pintype "passive"))
      (node (ref "J4") (pin "P7") (pinfunction "DAT0_P7") (pintype "bidirectional"))
      (node (ref "R8") (pin "1") (pinfunction "1_1") (pintype "passive"))
      (node (ref "TP6") (pin "TP") (pinfunction "TP_TP") (pintype "input"))
      (node (ref "U1") (pin "2") (pinfunction "DO(IO1)_2") (pintype "bidirectional"))
      (node (ref "U2") (pin "27") (pinfunction "IO2_27") (pintype "bidirectional"))
    )
    (net (code "21") (name "MOSI") (class "Default")
      (node (ref "D11") (pin "2") (pinfunction "2_2") (pintype "passive"))
      (node (ref "J1") (pin "14") (pinfunction "14_14") (pintype "bidirectional"))
      (node (ref "J4") (pin "P3") (pinfunction "CMD_P3") (pintype "bidirectional"))
      (node (ref "R7") (pin "1") (pinfunction "1_1") (pintype "passive"))
      (node (ref "TP7") (pin "TP") (pinfunction "TP_TP") (pintype "input"))
      (node (ref "U1") (pin "5") (pinfunction "DI(IO0)_5") (pintype "bidirectional"))
      (node (ref "U2") (pin "7") (pinfunction "IO7_7") (pintype "bidirectional"))
    )
    (net (code "22") (name "Net-(CHG_LED-PadC)") (class "Default")
      (node (ref "CHG_LED") (pin "C") (pinfunction "C_C") (pintype "passive"))
      (node (ref "R1_BAT") (pin "1") (pinfunction "1_1") (pintype "passive"))
    )
    (net (code "23") (name "Net-(D2-CATHODE)") (class "Default")
      (node (ref "C1_BAT1") (pin "1") (pinfunction "1_1") (pintype "passive"))
      (node (ref "D2") (pin "1") (pinfunction "CATHODE_1") (pintype "bidirectional"))
      (node (ref "IC4") (pin "1") (pinfunction "VIN_1") (pintype "bidirectional"))
      (node (ref "IC4") (pin "3") (pinfunction "CE_3") (pintype "bidirectional"))
      (node (ref "Q1") (pin "2") (pinfunction "S_2") (pintype "bidirectional"))
    )
    (net (code "24") (name "Net-(D3-A)") (class "Default")
      (node (ref "C4") (pin "1") (pinfunction "1_1") (pintype "passive"))
      (node (ref "D3") (pin "2") (pinfunction "A_2") (pintype "bidirectional"))
      (node (ref "D4") (pin "1") (pinfunction "K_1") (pintype "bidirectional"))
    )
    (net (code "25") (name "Net-(D7-CATHODE)") (class "Default")
      (node (ref "D7") (pin "1") (pinfunction "CATHODE_1") (pintype "bidirectional"))
      (node (ref "R_CAPACITOR") (pin "1") (pinfunction "1_1") (pintype "passive"))
    )
    (net (code "26") (name "Net-(EPD_C1-Pad1)") (class "Default")
      (node (ref "EPD_C1") (pin "1") (pinfunction "1_1") (pintype "passive"))
      (node (ref "J1") (pin "4") (pinfunction "4_4") (pintype "bidirectional"))
    )
    (net (code "27") (name "Net-(EPD_C2-Pad1)") (class "Default")
      (node (ref "EPD_C2") (pin "1") (pinfunction "1_1") (pintype "passive"))
      (node (ref "J1") (pin "5") (pinfunction "5_5") (pintype "bidirectional"))
    )
    (net (code "28") (name "Net-(EPD_C6-Pad1)") (class "Default")
      (node (ref "EPD_C6") (pin "1") (pinfunction "1_1") (pintype "passive"))
      (node (ref "J1") (pin "18") (pinfunction "18_18") (pintype "bidirectional"))
    )
    (net (code "29") (name "Net-(EPD_C7-Pad1)") (class "Default")
      (node (ref "EPD_C7") (pin "1") (pinfunction "1_1") (pintype "passive"))
      (node (ref "J1") (pin "19") (pinfunction "19_19") (pintype "bidirectional"))
    )
    (net (code "30") (name "Net-(EPD_C8-Pad1)") (class "Default")
      (node (ref "EPD_C8") (pin "1") (pinfunction "1_1") (pintype "passive"))
      (node (ref "J1") (pin "20") (pinfunction "20_20") (pintype "bidirectional"))
    )
    (net (code "31") (name "Net-(EPD_C10-Pad1)") (class "Default")
      (node (ref "EPD_C10") (pin "1") (pinfunction "1_1") (pintype "passive"))
      (node (ref "J1") (pin "22") (pinfunction "22_22") (pintype "bidirectional"))
    )
    (net (code "32") (name "Net-(EPD_C12-Pad1)") (class "Default")
      (node (ref "EPD_C12") (pin "1") (pinfunction "1_1") (pintype "passive"))
      (node (ref "J1") (pin "24") (pinfunction "24_24") (pintype "bidirectional"))
    )
    (net (code "33") (name "Net-(IC1-CT)") (class "Default")
      (node (ref "C_DELAY") (pin "1") (pinfunction "1_1") (pintype "passive"))
      (node (ref "IC1") (pin "5") (pinfunction "CT_5") (pintype "bidirectional"))
    )
    (net (code "34") (name "Net-(J2-PadA5)") (class "Default")
      (node (ref "J2") (pin "A5") (pinfunction "A5_A5") (pintype "bidirectional"))
      (node (ref "R2-USB1") (pin "2") (pinfunction "2_2") (pintype "passive"))
    )
    (net (code "35") (name "Net-(J2-PadB5)") (class "Default")
      (node (ref "J2") (pin "B5") (pinfunction "B5_B5") (pintype "bidirectional"))
      (node (ref "R2-USB") (pin "1") (pinfunction "1_1") (pintype "passive"))
    )
    (net (code "36") (name "Net-(MCP73831-PROG)") (class "Default")
      (node (ref "MCP73831") (pin "5") (pinfunction "PROG_5") (pintype "input"))
      (node (ref "R2_BAT") (pin "2") (pinfunction "2_2") (pintype "passive"))
    )
    (net (code "37") (name "Net-(MCP73831-STAT)") (class "Default")
      (node (ref "MCP73831") (pin "1") (pinfunction "STAT_1") (pintype "output"))
      (node (ref "R1_BAT") (pin "2") (pinfunction "2_2") (pintype "passive"))
    )
    (net (code "38") (name "Net-(SENSOR2-CSB)") (class "Default")
      (node (ref "SENSOR2") (pin "2") (pinfunction "CSB_2") (pintype "input"))
      (node (ref "SENSOR2") (pin "8") (pinfunction "VDD_8") (pintype "power_in"))
    )
    (net (code "39") (name "PREVGH") (class "Default")
      (node (ref "D5") (pin "1") (pinfunction "K_1") (pintype "bidirectional"))
      (node (ref "EPD_C9") (pin "1") (pinfunction "1_1") (pintype "passive"))
      (node (ref "J1") (pin "21") (pinfunction "21_21") (pintype "bidirectional"))
    )
    (net (code "40") (name "PREVGL") (class "Default")
      (node (ref "D4") (pin "2") (pinfunction "A_2") (pintype "bidirectional"))
      (node (ref "EPD_C11") (pin "1") (pinfunction "1_1") (pintype "passive"))
      (node (ref "J1") (pin "23") (pinfunction "23_23") (pintype "bidirectional"))
    )
    (net (code "41") (name "RESE") (class "Default")
      (node (ref "J1") (pin "3") (pinfunction "3_3") (pintype "bidirectional"))
      (node (ref "Q3") (pin "2") (pinfunction "S_2") (pintype "bidirectional"))
      (node (ref "R3") (pin "2") (pinfunction "2_2") (pintype "passive"))
    )
    (net (code "42") (name "RESE'") (class "Default")
      (node (ref "R2") (pin "2") (pinfunction "2_2") (pintype "passive"))
      (node (ref "R3") (pin "1") (pinfunction "1_1") (pintype "passive"))
      (node (ref "SJ1") (pin "2") (pinfunction "2_2") (pintype "passive"))
    )
    (net (code "43") (name "RESET") (class "Default")
      (node (ref "C5") (pin "1") (pinfunction "1_1") (pintype "passive"))
      (node (ref "IC1") (pin "1") (pinfunction "VOUT_1") (pintype "bidirectional"))
      (node (ref "RESET_BUTTON") (pin "3") (pinfunction "3_3") (pintype "passive"))
      (node (ref "RESET_BUTTON") (pin "4") (pinfunction "4_4") (pintype "passive"))
      (node (ref "R_RESET") (pin "1") (pinfunction "1_1") (pintype "passive"))
      (node (ref "U2") (pin "3") (pinfunction "EN_3") (pintype "input"))
    )
    (net (code "44") (name "RTC_RST") (class "Default")
      (node (ref "U2") (pin "16") (pinfunction "IO18_16") (pintype "bidirectional"))
      (node (ref "U3") (pin "4") (pinfunction "~{RST}_4") (pintype "input"))
    )
    (net (code "45") (name "RX") (class "Default")
      (node (ref "TP2") (pin "TP") (pinfunction "TP_TP") (pintype "input"))
      (node (ref "U2") (pin "24") (pinfunction "RXD0/GPIO17_24") (pintype "bidirectional"))
    )
    (net (code "46") (name "SCK") (class "Default")
      (node (ref "D10") (pin "2") (pinfunction "2_2") (pintype "passive"))
      (node (ref "J1") (pin "13") (pinfunction "13_13") (pintype "bidirectional"))
      (node (ref "J4") (pin "P5") (pinfunction "CLK_P5") (pintype "bidirectional"))
      (node (ref "R6") (pin "1") (pinfunction "1_1") (pintype "passive"))
      (node (ref "TP8") (pin "TP") (pinfunction "TP_TP") (pintype "input"))
      (node (ref "U1") (pin "6") (pinfunction "CLK_6") (pintype "input"))
      (node (ref "U2") (pin "6") (pinfunction "IO6_6") (pintype "bidirectional"))
    )
    (net (code "47") (name "SCL") (class "Default")
      (node (ref "J3") (pin "4") (pinfunction "4_4") (pintype "passive"))
      (node (ref "R2-PINH") (pin "1") (pinfunction "1_1") (pintype "passive"))
      (node (ref "SENSOR2") (pin "4") (pinfunction "SCK_4") (pintype "input"))
      (node (ref "U2") (pin "20") (pinfunction "IO22_20") (pintype "bidirectional"))
      (node (ref "U3") (pin "16") (pinfunction "SCL_16") (pintype "input"))
      (node (ref "U4") (pin "7") (pinfunction "SCL_7") (pintype "input"))
    )
    (net (code "48") (name "SDA") (class "Default")
      (node (ref "J3") (pin "3") (pinfunction "3_3") (pintype "passive"))
      (node (ref "R1_PINH") (pin "1") (pinfunction "1_1") (pintype "passive"))
      (node (ref "SENSOR2") (pin "3") (pinfunction "SDI_3") (pintype "bidirectional"))
      (node (ref "U2") (pin "19") (pinfunction "IO21_19") (pintype "bidirectional"))
      (node (ref "U3") (pin "15") (pinfunction "SDA_15") (pintype "bidirectional"))
      (node (ref "U4") (pin "8") (pinfunction "SDA_8") (pintype "bidirectional"))
    )
    (net (code "49") (name "SRC") (class "Default")
      (node (ref "C4") (pin "2") (pinfunction "2_2") (pintype "passive"))
      (node (ref "D5") (pin "2") (pinfunction "A_2") (pintype "bidirectional"))
      (node (ref "L1") (pin "1") (pinfunction "1_1") (pintype "passive"))
      (node (ref "Q3") (pin "3") (pinfunction "D_3") (pintype "bidirectional"))
    )
    (net (code "50") (name "SS_SD") (class "Default")
      (node (ref "D8") (pin "2") (pinfunction "2_2") (pintype "passive"))
      (node (ref "J4") (pin "P2") (pinfunction "CD/DAT3_P2") (pintype "bidirectional"))
      (node (ref "R10") (pin "1") (pinfunction "1_1") (pintype "passive"))
      (node (ref "U2") (pin "4") (pinfunction "IO4_4") (pintype "bidirectional"))
    )
    (net (code "51") (name "TX") (class "Default")
      (node (ref "TP1") (pin "TP") (pinfunction "TP_TP") (pintype "input"))
      (node (ref "U2") (pin "25") (pinfunction "TXD0/GPIO16_25") (pintype "bidirectional"))
    )
    (net (code "52") (name "USB_D+") (class "Default")
      (node (ref "D1") (pin "1") (pinfunction "I/O1_1_1") (pintype "bidirectional"))
      (node (ref "U2") (pin "14") (pinfunction "IO13_14") (pintype "bidirectional"))
    )
    (net (code "53") (name "USB_D-") (class "Default")
      (node (ref "D1") (pin "3") (pinfunction "I/O2_1_3") (pintype "bidirectional"))
      (node (ref "U2") (pin "13") (pinfunction "IO12_13") (pintype "bidirectional"))
    )
    (net (code "54") (name "VBAT") (class "Default")
      (node (ref "C2_BAT") (pin "1") (pinfunction "1_1") (pintype "passive"))
      (node (ref "MCP73831") (pin "3") (pinfunction "VBAT_3") (pintype "power_in"))
      (node (ref "Q1") (pin "3") (pinfunction "D_3") (pintype "bidirectional"))
      (node (ref "TP3") (pin "TP") (pinfunction "TP_TP") (pintype "input"))
      (node (ref "U4") (pin "2") (pinfunction "CELL_2") (pintype "power_in"))
      (node (ref "U4") (pin "3") (pinfunction "VDD_3") (pintype "power_in"))
    )
    (net (code "55") (name "VBUS") (class "Default")
      (node (ref "C1_BAT") (pin "1") (pinfunction "1_1") (pintype "passive"))
      (node (ref "C4_USB") (pin "1") (pinfunction "1_1") (pintype "passive"))
      (node (ref "C5_USB") (pin "1") (pinfunction "1_1") (pintype "passive"))
      (node (ref "CHG_LED") (pin "A") (pinfunction "A_A") (pintype "passive"))
      (node (ref "D1") (pin "5") (pinfunction "VBUS_5") (pintype "bidirectional"))
      (node (ref "D2") (pin "2") (pinfunction "ANODE_2") (pintype "bidirectional"))
      (node (ref "MCP73831") (pin "4") (pinfunction "VIN_4") (pintype "power_in"))
      (node (ref "PFMF.050.1") (pin "2") (pinfunction "2_2") (pintype "passive"))
      (node (ref "Q1") (pin "1") (pinfunction "G_1") (pintype "bidirectional"))
      (node (ref "R1_PWRUSB") (pin "2") (pinfunction "2_2") (pintype "passive"))
      (node (ref "TP14") (pin "TP") (pinfunction "TP_TP") (pintype "input"))
    )
    (net (code "56") (name "VRTC") (class "Default")
      (node (ref "C10_SUPERCAP") (pin "2") (pinfunction "2_2") (pintype "passive"))
      (node (ref "C8") (pin "1") (pinfunction "1_1") (pintype "passive"))
      (node (ref "R_CAPACITOR") (pin "2") (pinfunction "2_2") (pintype "passive"))
      (node (ref "U3") (pin "14") (pinfunction "VBAT_14") (pintype "power_in"))
    )
    (net (code "57") (name "VUSB") (class "Default")
      (node (ref "J2") (pin "A4") (pinfunction "A4_A4") (pintype "bidirectional"))
      (node (ref "J2") (pin "A9") (pinfunction "A9_A9") (pintype "bidirectional"))
      (node (ref "J2") (pin "B4") (pinfunction "B4_B4") (pintype "bidirectional"))
      (node (ref "J2") (pin "B9") (pinfunction "B9_B9") (pintype "bidirectional"))
      (node (ref "PFMF.050.1") (pin "1") (pinfunction "1_1") (pintype "passive"))
    )
    (net (code "58") (name "unconnected-(IC1-NC-Pad4)") (class "Default")
      (node (ref "IC1") (pin "4") (pinfunction "NC_4") (pintype "no_connect"))
    )
    (net (code "59") (name "unconnected-(IC4-NC-Pad4)") (class "Default")
      (node (ref "IC4") (pin "4") (pinfunction "NC_4") (pintype "no_connect"))
    )
    (net (code "60") (name "unconnected-(J1-Pad1)") (class "Default")
      (node (ref "J1") (pin "1") (pinfunction "1_1") (pintype "bidirectional"))
    )
    (net (code "61") (name "unconnected-(J1-Pad6)") (class "Default")
      (node (ref "J1") (pin "6") (pinfunction "6_6") (pintype "bidirectional"))
    )
    (net (code "62") (name "unconnected-(J1-Pad7)") (class "Default")
      (node (ref "J1") (pin "7") (pinfunction "7_7") (pintype "bidirectional"))
    )
    (net (code "63") (name "unconnected-(J2-PadA8)") (class "Default")
      (node (ref "J2") (pin "A8") (pinfunction "A8_A8") (pintype "bidirectional"))
    )
    (net (code "64") (name "unconnected-(J2-PadB8)") (class "Default")
      (node (ref "J2") (pin "B8") (pinfunction "B8_B8") (pintype "bidirectional"))
    )
    (net (code "65") (name "unconnected-(J4-DAT1-PadP8)") (class "Default")
      (node (ref "J4") (pin "P8") (pinfunction "DAT1_P8") (pintype "bidirectional"))
    )
    (net (code "66") (name "unconnected-(J4-DAT2-PadP1)") (class "Default")
      (node (ref "J4") (pin "P1") (pinfunction "DAT2_P1") (pintype "bidirectional"))
    )
    (net (code "67") (name "unconnected-(J4-DETECTION_1-PadS1)") (class "Default")
      (node (ref "J4") (pin "S1") (pinfunction "DETECTION_1_S1") (pintype "bidirectional"))
    )
    (net (code "68") (name "unconnected-(J4-DETECTION_2-PadS2)") (class "Default")
      (node (ref "J4") (pin "S2") (pinfunction "DETECTION_2_S2") (pintype "bidirectional"))
    )
    (net (code "69") (name "unconnected-(U2-NC-Pad22)") (class "Default")
      (node (ref "U2") (pin "22") (pinfunction "NC_22") (pintype "no_connect"))
    )
    (net (code "70") (name "unconnected-(U4-~{ALERT}-Pad5)") (class "Default")
      (node (ref "U4") (pin "5") (pinfunction "~{ALERT}_5") (pintype "output"))
    )
  )
)
